# 1TTR4---_Cumbo_Fabio_---_PIC_Simple.net
KiCad netlist of a schematic drawn in EAGLE
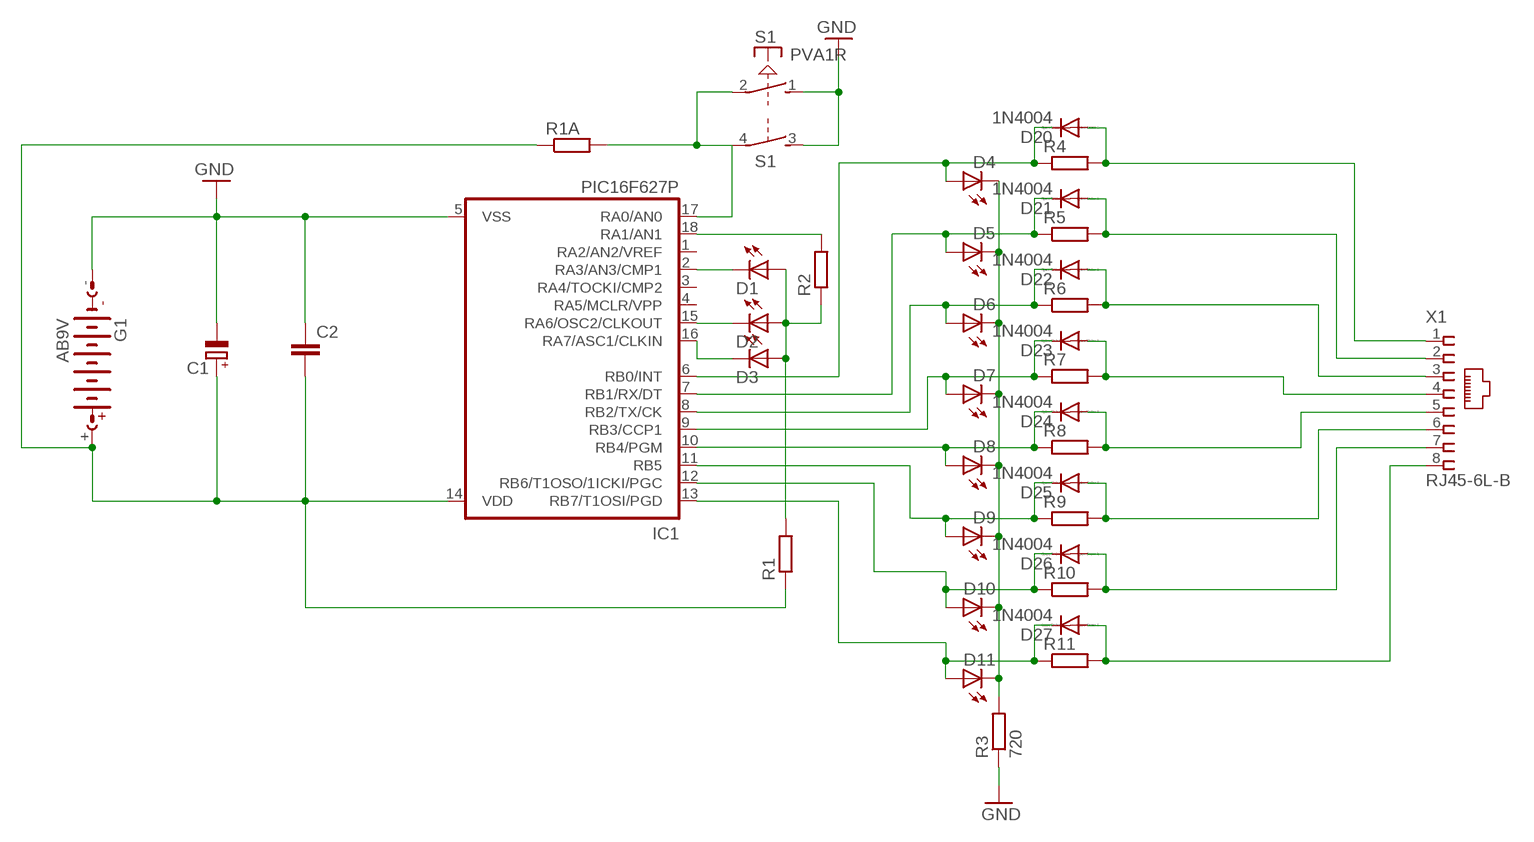
[diagram p0: schematic, sheet 1]

(export (version "E")
  (design (tool "Eeschema 10.0.6"))
  (components
    (comp (ref "C1")
      (value "CPOL-EUE5-6")
      (footprint "eagle-import:E5-6")
      (libsource (lib "eagle-import") (part "CPOL-EUE5-6"))
    )
    (comp (ref "C2")
      (value "C-EU050-024X044")
      (footprint "eagle-import:C050-024X044")
      (libsource (lib "eagle-import") (part "C-EU050-024X044"))
    )
    (comp (ref "D1")
      (value "LED5MM")
      (footprint "eagle-import:LED5MM")
      (libsource (lib "eagle-import") (part "LED5MM"))
    )
    (comp (ref "D2")
      (value "LED5MM")
      (footprint "eagle-import:LED5MM")
      (libsource (lib "eagle-import") (part "LED5MM"))
    )
    (comp (ref "D3")
      (value "LED5MM")
      (footprint "eagle-import:LED5MM")
      (libsource (lib "eagle-import") (part "LED5MM"))
    )
    (comp (ref "D4")
      (value "LED5MM")
      (footprint "eagle-import:LED5MM")
      (libsource (lib "eagle-import") (part "LED5MM"))
    )
    (comp (ref "D5")
      (value "LED5MM")
      (footprint "eagle-import:LED5MM")
      (libsource (lib "eagle-import") (part "LED5MM"))
    )
    (comp (ref "D6")
      (value "LED5MM")
      (footprint "eagle-import:LED5MM")
      (libsource (lib "eagle-import") (part "LED5MM"))
    )
    (comp (ref "D7")
      (value "LED5MM")
      (footprint "eagle-import:LED5MM")
      (libsource (lib "eagle-import") (part "LED5MM"))
    )
    (comp (ref "D8")
      (value "LED5MM")
      (footprint "eagle-import:LED5MM")
      (libsource (lib "eagle-import") (part "LED5MM"))
    )
    (comp (ref "D9")
      (value "LED5MM")
      (footprint "eagle-import:LED5MM")
      (libsource (lib "eagle-import") (part "LED5MM"))
    )
    (comp (ref "D10")
      (value "LED5MM")
      (footprint "eagle-import:LED5MM")
      (libsource (lib "eagle-import") (part "LED5MM"))
    )
    (comp (ref "D11")
      (value "LED5MM")
      (footprint "eagle-import:LED5MM")
      (libsource (lib "eagle-import") (part "LED5MM"))
    )
    (comp (ref "D20")
      (value "1N4004")
      (footprint "eagle-import:DO41-10")
      (libsource (lib "eagle-import") (part "1N4004"))
    )
    (comp (ref "D21")
      (value "1N4004")
      (footprint "eagle-import:DO41-10")
      (libsource (lib "eagle-import") (part "1N4004"))
    )
    (comp (ref "D22")
      (value "1N4004")
      (footprint "eagle-import:DO41-10")
      (libsource (lib "eagle-import") (part "1N4004"))
    )
    (comp (ref "D23")
      (value "1N4004")
      (footprint "eagle-import:DO41-10")
      (libsource (lib "eagle-import") (part "1N4004"))
    )
    (comp (ref "D24")
      (value "1N4004")
      (footprint "eagle-import:DO41-10")
      (libsource (lib "eagle-import") (part "1N4004"))
    )
    (comp (ref "D25")
      (value "1N4004")
      (footprint "eagle-import:DO41-10")
      (libsource (lib "eagle-import") (part "1N4004"))
    )
    (comp (ref "D26")
      (value "1N4004")
      (footprint "eagle-import:DO41-10")
      (libsource (lib "eagle-import") (part "1N4004"))
    )
    (comp (ref "D27")
      (value "1N4004")
      (footprint "eagle-import:DO41-10")
      (libsource (lib "eagle-import") (part "1N4004"))
    )
    (comp (ref "G1")
      (value "AB9V")
      (footprint "eagle-import:AB9V")
      (libsource (lib "eagle-import") (part "AB9V"))
    )
    (comp (ref "IC1")
      (value "PIC16F627P")
      (footprint "eagle-import:DIL18")
      (fields (field (name "MF") "MICROCHIP") (field (name "MPN") "PIC16F627-20I/P"))
      (libsource (lib "eagle-import") (part "PIC16F627P"))
    )
    (comp (ref "R1")
      (value "R-EU_0204/7")
      (footprint "eagle-import:0204_7")
      (libsource (lib "eagle-import") (part "R-EU_0204/7"))
    )
    (comp (ref "R1A")
      (value "R-EU_0204/7")
      (footprint "eagle-import:0204_7")
      (libsource (lib "eagle-import") (part "R-EU_0204/7"))
    )
    (comp (ref "R2")
      (value "R-EU_0204/7")
      (footprint "eagle-import:0204_7")
      (libsource (lib "eagle-import") (part "R-EU_0204/7"))
    )
    (comp (ref "R3")
      (value "720")
      (footprint "eagle-import:0204_7")
      (libsource (lib "eagle-import") (part "R-EU_0204/7"))
    )
    (comp (ref "R4")
      (value "R-EU_0204/7")
      (footprint "eagle-import:0204_7")
      (libsource (lib "eagle-import") (part "R-EU_0204/7"))
    )
    (comp (ref "R5")
      (value "R-EU_0204/7")
      (footprint "eagle-import:0204_7")
      (libsource (lib "eagle-import") (part "R-EU_0204/7"))
    )
    (comp (ref "R6")
      (value "R-EU_0204/7")
      (footprint "eagle-import:0204_7")
      (libsource (lib "eagle-import") (part "R-EU_0204/7"))
    )
    (comp (ref "R7")
      (value "R-EU_0204/7")
      (footprint "eagle-import:0204_7")
      (libsource (lib "eagle-import") (part "R-EU_0204/7"))
    )
    (comp (ref "R8")
      (value "R-EU_0204/7")
      (footprint "eagle-import:0204_7")
      (libsource (lib "eagle-import") (part "R-EU_0204/7"))
    )
    (comp (ref "R9")
      (value "R-EU_0204/7")
      (footprint "eagle-import:0204_7")
      (libsource (lib "eagle-import") (part "R-EU_0204/7"))
    )
    (comp (ref "R10")
      (value "R-EU_0204/7")
      (footprint "eagle-import:0204_7")
      (libsource (lib "eagle-import") (part "R-EU_0204/7"))
    )
    (comp (ref "R11")
      (value "R-EU_0204/7")
      (footprint "eagle-import:0204_7")
      (libsource (lib "eagle-import") (part "R-EU_0204/7"))
    )
    (comp (ref "S1")
      (value "PVA1R")
      (footprint "eagle-import:PVA1R")
      (libsource (lib "eagle-import") (part "PVA1R"))
    )
    (comp (ref "X1")
      (value "RJ45-6L-B")
      (footprint "eagle-import:RJ45-NO-SHIELD")
      (libsource (lib "eagle-import") (part "RJ45-6L-B"))
    )
  )
  (nets
    (net (code "1") (name "GND") (class "Default")
      (node (ref "C1") (pin "-") (pinfunction "-_-") (pintype "passive"))
      (node (ref "C2") (pin "1") (pinfunction "1_1") (pintype "passive"))
      (node (ref "G1") (pin "-") (pinfunction "-_-") (pintype "passive"))
      (node (ref "IC1") (pin "5") (pinfunction "VSS_5") (pintype "power_in"))
      (node (ref "R3") (pin "1") (pinfunction "1_1") (pintype "passive"))
      (node (ref "S1") (pin "1") (pinfunction "S_1") (pintype "passive"))
      (node (ref "S1") (pin "3") (pinfunction "S_3") (pintype "passive"))
    )
    (net (code "2") (name "Net-(D1-C)") (class "Default")
      (node (ref "D1") (pin "K") (pinfunction "C_K") (pintype "passive"))
      (node (ref "IC1") (pin "2") (pinfunction "RA3/AN3/CMP1_2") (pintype "bidirectional"))
    )
    (net (code "3") (name "Net-(D1-PadA)") (class "Default")
      (node (ref "D1") (pin "A") (pinfunction "A_A") (pintype "passive"))
      (node (ref "D2") (pin "A") (pinfunction "A_A") (pintype "passive"))
      (node (ref "D3") (pin "A") (pinfunction "A_A") (pintype "passive"))
      (node (ref "R1") (pin "2") (pinfunction "2_2") (pintype "passive"))
      (node (ref "R2") (pin "1") (pinfunction "1_1") (pintype "passive"))
    )
    (net (code "4") (name "Net-(D2-C)") (class "Default")
      (node (ref "D2") (pin "K") (pinfunction "C_K") (pintype "passive"))
      (node (ref "IC1") (pin "15") (pinfunction "RA6/OSC2/CLKOUT_15") (pintype "bidirectional"))
    )
    (net (code "5") (name "Net-(D3-C)") (class "Default")
      (node (ref "D3") (pin "K") (pinfunction "C_K") (pintype "passive"))
      (node (ref "IC1") (pin "16") (pinfunction "RA7/ASC1/CLKIN_16") (pintype "bidirectional"))
    )
    (net (code "6") (name "Net-(D10-C)") (class "Default")
      (node (ref "D10") (pin "K") (pinfunction "C_K") (pintype "passive"))
      (node (ref "D11") (pin "K") (pinfunction "C_K") (pintype "passive"))
      (node (ref "D4") (pin "K") (pinfunction "C_K") (pintype "passive"))
      (node (ref "D5") (pin "K") (pinfunction "C_K") (pintype "passive"))
      (node (ref "D6") (pin "K") (pinfunction "C_K") (pintype "passive"))
      (node (ref "D7") (pin "K") (pinfunction "C_K") (pintype "passive"))
      (node (ref "D8") (pin "K") (pinfunction "C_K") (pintype "passive"))
      (node (ref "D9") (pin "K") (pinfunction "C_K") (pintype "passive"))
      (node (ref "R3") (pin "2") (pinfunction "2_2") (pintype "passive"))
    )
    (net (code "7") (name "Net-(D20-PadA)") (class "Default")
      (node (ref "D20") (pin "A") (pinfunction "A_A") (pintype "passive"))
      (node (ref "R4") (pin "2") (pinfunction "2_2") (pintype "passive"))
      (node (ref "X1") (pin "1") (pinfunction "1_1") (pintype "passive"))
    )
    (net (code "8") (name "Net-(D21-PadA)") (class "Default")
      (node (ref "D21") (pin "A") (pinfunction "A_A") (pintype "passive"))
      (node (ref "R5") (pin "2") (pinfunction "2_2") (pintype "passive"))
      (node (ref "X1") (pin "2") (pinfunction "2_2") (pintype "passive"))
    )
    (net (code "9") (name "Net-(D22-PadA)") (class "Default")
      (node (ref "D22") (pin "A") (pinfunction "A_A") (pintype "passive"))
      (node (ref "R6") (pin "2") (pinfunction "2_2") (pintype "passive"))
      (node (ref "X1") (pin "3") (pinfunction "3_3") (pintype "passive"))
    )
    (net (code "10") (name "Net-(D23-PadA)") (class "Default")
      (node (ref "D23") (pin "A") (pinfunction "A_A") (pintype "passive"))
      (node (ref "R7") (pin "2") (pinfunction "2_2") (pintype "passive"))
      (node (ref "X1") (pin "4") (pinfunction "4_4") (pintype "passive"))
    )
    (net (code "11") (name "Net-(D24-PadA)") (class "Default")
      (node (ref "D24") (pin "A") (pinfunction "A_A") (pintype "passive"))
      (node (ref "R8") (pin "2") (pinfunction "2_2") (pintype "passive"))
      (node (ref "X1") (pin "5") (pinfunction "5_5") (pintype "passive"))
    )
    (net (code "12") (name "Net-(D25-PadA)") (class "Default")
      (node (ref "D25") (pin "A") (pinfunction "A_A") (pintype "passive"))
      (node (ref "R9") (pin "2") (pinfunction "2_2") (pintype "passive"))
      (node (ref "X1") (pin "6") (pinfunction "6_6") (pintype "passive"))
    )
    (net (code "13") (name "Net-(D26-PadA)") (class "Default")
      (node (ref "D26") (pin "A") (pinfunction "A_A") (pintype "passive"))
      (node (ref "R10") (pin "2") (pinfunction "2_2") (pintype "passive"))
      (node (ref "X1") (pin "7") (pinfunction "7_7") (pintype "passive"))
    )
    (net (code "14") (name "Net-(D27-PadA)") (class "Default")
      (node (ref "D27") (pin "A") (pinfunction "A_A") (pintype "passive"))
      (node (ref "R11") (pin "2") (pinfunction "2_2") (pintype "passive"))
      (node (ref "X1") (pin "8") (pinfunction "8_8") (pintype "passive"))
    )
    (net (code "15") (name "Net-(IC1-RA0{slash}AN0)") (class "Default")
      (node (ref "IC1") (pin "17") (pinfunction "RA0/AN0_17") (pintype "bidirectional"))
      (node (ref "R1A") (pin "2") (pinfunction "2_2") (pintype "passive"))
      (node (ref "S1") (pin "2") (pinfunction "P_2") (pintype "passive"))
      (node (ref "S1") (pin "4") (pinfunction "P_4") (pintype "passive"))
    )
    (net (code "16") (name "Net-(IC1-RA1{slash}AN1)") (class "Default")
      (node (ref "IC1") (pin "18") (pinfunction "RA1/AN1_18") (pintype "bidirectional"))
      (node (ref "R2") (pin "2") (pinfunction "2_2") (pintype "passive"))
    )
    (net (code "17") (name "Net-(IC1-RB0{slash}INT)") (class "Default")
      (node (ref "D20") (pin "C") (pinfunction "C_C") (pintype "passive"))
      (node (ref "D4") (pin "A") (pinfunction "A_A") (pintype "passive"))
      (node (ref "IC1") (pin "6") (pinfunction "RB0/INT_6") (pintype "bidirectional"))
      (node (ref "R4") (pin "1") (pinfunction "1_1") (pintype "passive"))
    )
    (net (code "18") (name "Net-(IC1-RB1{slash}RX{slash}DT)") (class "Default")
      (node (ref "D21") (pin "C") (pinfunction "C_C") (pintype "passive"))
      (node (ref "D5") (pin "A") (pinfunction "A_A") (pintype "passive"))
      (node (ref "IC1") (pin "7") (pinfunction "RB1/RX/DT_7") (pintype "bidirectional"))
      (node (ref "R5") (pin "1") (pinfunction "1_1") (pintype "passive"))
    )
    (net (code "19") (name "Net-(IC1-RB2{slash}TX{slash}CK)") (class "Default")
      (node (ref "D22") (pin "C") (pinfunction "C_C") (pintype "passive"))
      (node (ref "D6") (pin "A") (pinfunction "A_A") (pintype "passive"))
      (node (ref "IC1") (pin "8") (pinfunction "RB2/TX/CK_8") (pintype "bidirectional"))
      (node (ref "R6") (pin "1") (pinfunction "1_1") (pintype "passive"))
    )
    (net (code "20") (name "Net-(IC1-RB3{slash}CCP1)") (class "Default")
      (node (ref "D23") (pin "C") (pinfunction "C_C") (pintype "passive"))
      (node (ref "D7") (pin "A") (pinfunction "A_A") (pintype "passive"))
      (node (ref "IC1") (pin "9") (pinfunction "RB3/CCP1_9") (pintype "bidirectional"))
      (node (ref "R7") (pin "1") (pinfunction "1_1") (pintype "passive"))
    )
    (net (code "21") (name "Net-(IC1-RB4{slash}PGM)") (class "Default")
      (node (ref "D24") (pin "C") (pinfunction "C_C") (pintype "passive"))
      (node (ref "D8") (pin "A") (pinfunction "A_A") (pintype "passive"))
      (node (ref "IC1") (pin "10") (pinfunction "RB4/PGM_10") (pintype "bidirectional"))
      (node (ref "R8") (pin "1") (pinfunction "1_1") (pintype "passive"))
    )
    (net (code "22") (name "Net-(IC1-RB5)") (class "Default")
      (node (ref "D25") (pin "C") (pinfunction "C_C") (pintype "passive"))
      (node (ref "D9") (pin "A") (pinfunction "A_A") (pintype "passive"))
      (node (ref "IC1") (pin "11") (pinfunction "RB5_11") (pintype "bidirectional"))
      (node (ref "R9") (pin "1") (pinfunction "1_1") (pintype "passive"))
    )
    (net (code "23") (name "Net-(IC1-RB6{slash}T1OSO{slash}1ICKI{slash}PGC)") (class "Default")
      (node (ref "D10") (pin "A") (pinfunction "A_A") (pintype "passive"))
      (node (ref "D26") (pin "C") (pinfunction "C_C") (pintype "passive"))
      (node (ref "IC1") (pin "12") (pinfunction "RB6/T1OSO/1ICKI/PGC_12") (pintype "bidirectional"))
      (node (ref "R10") (pin "1") (pinfunction "1_1") (pintype "passive"))
    )
    (net (code "24") (name "Net-(IC1-RB7{slash}T1OSI{slash}PGD)") (class "Default")
      (node (ref "D11") (pin "A") (pinfunction "A_A") (pintype "passive"))
      (node (ref "D27") (pin "C") (pinfunction "C_C") (pintype "passive"))
      (node (ref "IC1") (pin "13") (pinfunction "RB7/T1OSI/PGD_13") (pintype "bidirectional"))
      (node (ref "R11") (pin "1") (pinfunction "1_1") (pintype "passive"))
    )
    (net (code "25") (name "Net-(IC1-VDD)") (class "Default")
      (node (ref "C1") (pin "+") (pinfunction "+_+") (pintype "passive"))
      (node (ref "C2") (pin "2") (pinfunction "2_2") (pintype "passive"))
      (node (ref "G1") (pin "+") (pinfunction "+_+") (pintype "passive"))
      (node (ref "IC1") (pin "14") (pinfunction "VDD_14") (pintype "power_in"))
      (node (ref "R1") (pin "1") (pinfunction "1_1") (pintype "passive"))
      (node (ref "R1A") (pin "1") (pinfunction "1_1") (pintype "passive"))
    )
    (net (code "26") (name "unconnected-(IC1-RA2{slash}AN2{slash}VREF-Pad1)") (class "Default")
      (node (ref "IC1") (pin "1") (pinfunction "RA2/AN2/VREF_1") (pintype "bidirectional"))
    )
    (net (code "27") (name "unconnected-(IC1-RA4{slash}TOCKI{slash}CMP2-Pad3)") (class "Default")
      (node (ref "IC1") (pin "3") (pinfunction "RA4/TOCKI/CMP2_3") (pintype "bidirectional"))
    )
    (net (code "28") (name "unconnected-(IC1-RA5{slash}MCLR{slash}VPP-Pad4)") (class "Default")
      (node (ref "IC1") (pin "4") (pinfunction "RA5/MCLR/VPP_4") (pintype "input"))
    )
  )
)
